# PCB.net
KiCad netlist of a schematic drawn in EAGLE
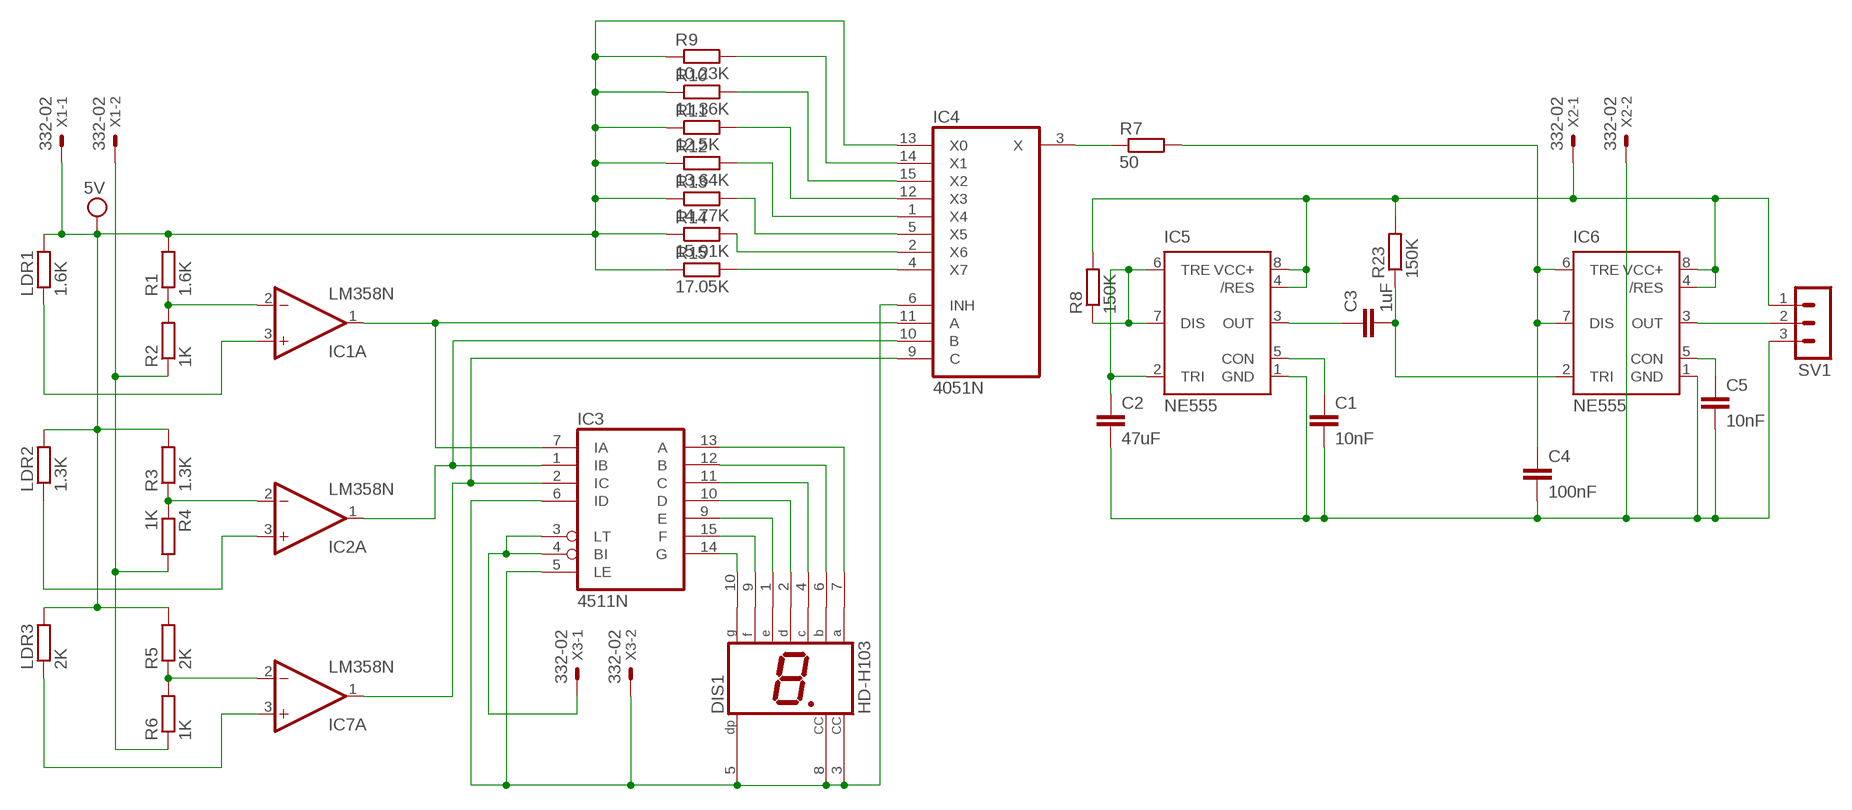
[diagram p0: schematic, sheet 1]

(export (version "E")
  (design (tool "Eeschema 10.0.6"))
  (components
    (comp (ref "C1")
      (value "10nF")
      (footprint "eagle-import:C2.5-2")
      (libsource (lib "eagle-import") (part "C2.5/2"))
    )
    (comp (ref "C2")
      (value "47uF")
      (footprint "eagle-import:C2.5-2")
      (libsource (lib "eagle-import") (part "C2.5/2"))
    )
    (comp (ref "C3")
      (value "1uF")
      (footprint "eagle-import:C2.5-2")
      (libsource (lib "eagle-import") (part "C2.5/2"))
    )
    (comp (ref "C4")
      (value "100nF")
      (footprint "eagle-import:C2.5-2")
      (libsource (lib "eagle-import") (part "C2.5/2"))
    )
    (comp (ref "C5")
      (value "10nF")
      (footprint "eagle-import:C2.5-2")
      (libsource (lib "eagle-import") (part "C2.5/2"))
    )
    (comp (ref "DIS1")
      (value "HD-H103")
      (footprint "eagle-import:HDSP-M")
      (libsource (lib "eagle-import") (part "HD-H103"))
    )
    (comp (ref "IC1")
      (value "LM358N")
      (footprint "eagle-import:DIL08")
      (libsource (lib "eagle-import") (part "LM358N"))
    )
    (comp (ref "IC2")
      (value "LM358N")
      (footprint "eagle-import:DIL08")
      (libsource (lib "eagle-import") (part "LM358N"))
    )
    (comp (ref "IC3")
      (value "4511N")
      (footprint "eagle-import:DIL16")
      (libsource (lib "eagle-import") (part "4511N"))
    )
    (comp (ref "IC4")
      (value "4051N")
      (footprint "eagle-import:DIL16")
      (libsource (lib "eagle-import") (part "4051N"))
    )
    (comp (ref "IC5")
      (value "NE555")
      (footprint "eagle-import:DIL-08")
      (fields (field (name "MF") "Arrow Electronics") (field (name "MPN") "NE555N"))
      (libsource (lib "eagle-import") (part "NE555"))
    )
    (comp (ref "IC6")
      (value "NE555")
      (footprint "eagle-import:DIL-08")
      (fields (field (name "MF") "Arrow Electronics") (field (name "MPN") "NE555N"))
      (libsource (lib "eagle-import") (part "NE555"))
    )
    (comp (ref "IC7")
      (value "LM358N")
      (footprint "eagle-import:DIL08")
      (libsource (lib "eagle-import") (part "LM358N"))
    )
    (comp (ref "LDR1")
      (value "1.6K")
      (footprint "eagle-import:0207_10")
      (libsource (lib "eagle-import") (part "R-EU_0207/10"))
    )
    (comp (ref "LDR2")
      (value "1.3K")
      (footprint "eagle-import:0207_10")
      (libsource (lib "eagle-import") (part "R-EU_0207/10"))
    )
    (comp (ref "LDR3")
      (value "2K")
      (footprint "eagle-import:0207_10")
      (libsource (lib "eagle-import") (part "R-EU_0207/10"))
    )
    (comp (ref "R1")
      (value "1.6K")
      (footprint "eagle-import:0207_10")
      (libsource (lib "eagle-import") (part "R-EU_0207/10"))
    )
    (comp (ref "R2")
      (value "1K")
      (footprint "eagle-import:0207_10")
      (libsource (lib "eagle-import") (part "R-EU_0207/10"))
    )
    (comp (ref "R3")
      (value "1.3K")
      (footprint "eagle-import:0207_10")
      (libsource (lib "eagle-import") (part "R-EU_0207/10"))
    )
    (comp (ref "R4")
      (value "1K")
      (footprint "eagle-import:0207_10")
      (libsource (lib "eagle-import") (part "R-EU_0207/10"))
    )
    (comp (ref "R5")
      (value "2K")
      (footprint "eagle-import:0207_10")
      (libsource (lib "eagle-import") (part "R-EU_0207/10"))
    )
    (comp (ref "R6")
      (value "1K")
      (footprint "eagle-import:0207_10")
      (libsource (lib "eagle-import") (part "R-EU_0207/10"))
    )
    (comp (ref "R7")
      (value "50")
      (footprint "eagle-import:0207_10")
      (libsource (lib "eagle-import") (part "R-EU_0207/10"))
    )
    (comp (ref "R8")
      (value "150K")
      (footprint "eagle-import:0207_10")
      (libsource (lib "eagle-import") (part "R-EU_0207/10"))
    )
    (comp (ref "R9")
      (value "10.23K")
      (footprint "eagle-import:0207_10")
      (libsource (lib "eagle-import") (part "R-EU_0207/10"))
    )
    (comp (ref "R10")
      (value "11.36K")
      (footprint "eagle-import:0207_10")
      (libsource (lib "eagle-import") (part "R-EU_0207/10"))
    )
    (comp (ref "R11")
      (value "12.5K")
      (footprint "eagle-import:0207_10")
      (libsource (lib "eagle-import") (part "R-EU_0207/10"))
    )
    (comp (ref "R12")
      (value "13.64K")
      (footprint "eagle-import:0207_10")
      (libsource (lib "eagle-import") (part "R-EU_0207/10"))
    )
    (comp (ref "R13")
      (value "14.77K")
      (footprint "eagle-import:0207_10")
      (libsource (lib "eagle-import") (part "R-EU_0207/10"))
    )
    (comp (ref "R14")
      (value "15.91K")
      (footprint "eagle-import:0207_10")
      (libsource (lib "eagle-import") (part "R-EU_0207/10"))
    )
    (comp (ref "R15")
      (value "17.05K")
      (footprint "eagle-import:0207_10")
      (libsource (lib "eagle-import") (part "R-EU_0207/10"))
    )
    (comp (ref "R23")
      (value "150K")
      (footprint "eagle-import:0207_10")
      (libsource (lib "eagle-import") (part "R-EU_0207/10"))
    )
    (comp (ref "SV1")
      (value "MA03-1")
      (footprint "eagle-import:MA03-1")
      (libsource (lib "eagle-import") (part "MA03-1"))
    )
    (comp (ref "X1")
      (value "332-02")
      (footprint "eagle-import:332-02")
      (libsource (lib "eagle-import") (part "332-02"))
    )
    (comp (ref "X2")
      (value "332-02")
      (footprint "eagle-import:332-02")
      (libsource (lib "eagle-import") (part "332-02"))
    )
    (comp (ref "X3")
      (value "332-02")
      (footprint "eagle-import:332-02")
      (libsource (lib "eagle-import") (part "332-02"))
    )
  )
  (nets
    (net (code "1") (name "5V") (class "Default")
      (node (ref "IC4") (pin "13") (pinfunction "X0_13") (pintype "bidirectional"))
      (node (ref "LDR1") (pin "2") (pinfunction "2_2") (pintype "passive"))
      (node (ref "LDR2") (pin "2") (pinfunction "2_2") (pintype "passive"))
      (node (ref "LDR3") (pin "2") (pinfunction "2_2") (pintype "passive"))
      (node (ref "R1") (pin "2") (pinfunction "2_2") (pintype "passive"))
      (node (ref "R10") (pin "1") (pinfunction "1_1") (pintype "passive"))
      (node (ref "R11") (pin "1") (pinfunction "1_1") (pintype "passive"))
      (node (ref "R12") (pin "1") (pinfunction "1_1") (pintype "passive"))
      (node (ref "R13") (pin "1") (pinfunction "1_1") (pintype "passive"))
      (node (ref "R14") (pin "1") (pinfunction "1_1") (pintype "passive"))
      (node (ref "R15") (pin "1") (pinfunction "1_1") (pintype "passive"))
      (node (ref "R3") (pin "2") (pinfunction "2_2") (pintype "passive"))
      (node (ref "R5") (pin "2") (pinfunction "2_2") (pintype "passive"))
      (node (ref "R9") (pin "1") (pinfunction "1_1") (pintype "passive"))
      (node (ref "X1") (pin "1") (pinfunction "S_1") (pintype "passive"))
    )
    (net (code "2") (name "Net-(DIS1-A)") (class "Default")
      (node (ref "DIS1") (pin "7") (pinfunction "A_7") (pintype "passive"))
      (node (ref "IC3") (pin "13") (pinfunction "A_13") (pintype "output"))
    )
    (net (code "3") (name "Net-(DIS1-B)") (class "Default")
      (node (ref "DIS1") (pin "6") (pinfunction "B_6") (pintype "passive"))
      (node (ref "IC3") (pin "12") (pinfunction "B_12") (pintype "output"))
    )
    (net (code "4") (name "Net-(DIS1-C)") (class "Default")
      (node (ref "DIS1") (pin "4") (pinfunction "C_4") (pintype "passive"))
      (node (ref "IC3") (pin "11") (pinfunction "C_11") (pintype "output"))
    )
    (net (code "5") (name "Net-(DIS1-D)") (class "Default")
      (node (ref "DIS1") (pin "2") (pinfunction "D_2") (pintype "passive"))
      (node (ref "IC3") (pin "10") (pinfunction "D_10") (pintype "output"))
    )
    (net (code "6") (name "Net-(DIS1-DP)") (class "Default")
      (node (ref "DIS1") (pin "3") (pinfunction "CC_3") (pintype "passive"))
      (node (ref "DIS1") (pin "5") (pinfunction "DP_5") (pintype "passive"))
      (node (ref "DIS1") (pin "8") (pinfunction "CC_8") (pintype "passive"))
      (node (ref "IC3") (pin "5") (pinfunction "LE_5") (pintype "input"))
      (node (ref "IC3") (pin "6") (pinfunction "ID_6") (pintype "input"))
      (node (ref "IC4") (pin "6") (pinfunction "INH_6") (pintype "input"))
      (node (ref "X3") (pin "2") (pinfunction "S_2") (pintype "passive"))
    )
    (net (code "7") (name "Net-(DIS1-E)") (class "Default")
      (node (ref "DIS1") (pin "1") (pinfunction "E_1") (pintype "passive"))
      (node (ref "IC3") (pin "9") (pinfunction "E_9") (pintype "output"))
    )
    (net (code "8") (name "Net-(DIS1-F)") (class "Default")
      (node (ref "DIS1") (pin "9") (pinfunction "F_9") (pintype "passive"))
      (node (ref "IC3") (pin "15") (pinfunction "F_15") (pintype "output"))
    )
    (net (code "9") (name "Net-(DIS1-G)") (class "Default")
      (node (ref "DIS1") (pin "10") (pinfunction "G_10") (pintype "passive"))
      (node (ref "IC3") (pin "14") (pinfunction "G_14") (pintype "output"))
    )
    (net (code "10") (name "Net-(IC1A-+IN)") (class "Default")
      (node (ref "IC1") (pin "3") (pinfunction "+IN_3") (pintype "input"))
      (node (ref "LDR1") (pin "1") (pinfunction "1_1") (pintype "passive"))
    )
    (net (code "11") (name "Net-(IC1A--IN)") (class "Default")
      (node (ref "IC1") (pin "2") (pinfunction "-IN_2") (pintype "input"))
      (node (ref "R1") (pin "1") (pinfunction "1_1") (pintype "passive"))
      (node (ref "R2") (pin "2") (pinfunction "2_2") (pintype "passive"))
    )
    (net (code "12") (name "Net-(IC1A-OUT)") (class "Default")
      (node (ref "IC1") (pin "1") (pinfunction "OUT_1") (pintype "output"))
      (node (ref "IC3") (pin "7") (pinfunction "IA_7") (pintype "input"))
      (node (ref "IC4") (pin "11") (pinfunction "A_11") (pintype "input"))
    )
    (net (code "13") (name "Net-(IC2A-+IN)") (class "Default")
      (node (ref "IC2") (pin "3") (pinfunction "+IN_3") (pintype "input"))
      (node (ref "LDR2") (pin "1") (pinfunction "1_1") (pintype "passive"))
    )
    (net (code "14") (name "Net-(IC2A--IN)") (class "Default")
      (node (ref "IC2") (pin "2") (pinfunction "-IN_2") (pintype "input"))
      (node (ref "R3") (pin "1") (pinfunction "1_1") (pintype "passive"))
      (node (ref "R4") (pin "1") (pinfunction "1_1") (pintype "passive"))
    )
    (net (code "15") (name "Net-(IC2A-OUT)") (class "Default")
      (node (ref "IC2") (pin "1") (pinfunction "OUT_1") (pintype "output"))
      (node (ref "IC3") (pin "1") (pinfunction "IB_1") (pintype "input"))
      (node (ref "IC4") (pin "10") (pinfunction "B_10") (pintype "input"))
    )
    (net (code "16") (name "Net-(IC3A-BI)") (class "Default")
      (node (ref "IC3") (pin "3") (pinfunction "LT_3") (pintype "input"))
      (node (ref "IC3") (pin "4") (pinfunction "BI_4") (pintype "input"))
      (node (ref "X3") (pin "1") (pinfunction "S_1") (pintype "passive"))
    )
    (net (code "17") (name "Net-(IC3A-IC)") (class "Default")
      (node (ref "IC3") (pin "2") (pinfunction "IC_2") (pintype "input"))
      (node (ref "IC4") (pin "9") (pinfunction "C_9") (pintype "input"))
      (node (ref "IC7") (pin "1") (pinfunction "OUT_1") (pintype "output"))
    )
    (net (code "18") (name "Net-(IC4A-X)") (class "Default")
      (node (ref "IC4") (pin "3") (pinfunction "X_3") (pintype "bidirectional"))
      (node (ref "R7") (pin "1") (pinfunction "1_1") (pintype "passive"))
    )
    (net (code "19") (name "Net-(IC4A-X1)") (class "Default")
      (node (ref "IC4") (pin "14") (pinfunction "X1_14") (pintype "bidirectional"))
      (node (ref "R9") (pin "2") (pinfunction "2_2") (pintype "passive"))
    )
    (net (code "20") (name "Net-(IC4A-X2)") (class "Default")
      (node (ref "IC4") (pin "15") (pinfunction "X2_15") (pintype "bidirectional"))
      (node (ref "R10") (pin "2") (pinfunction "2_2") (pintype "passive"))
    )
    (net (code "21") (name "Net-(IC4A-X3)") (class "Default")
      (node (ref "IC4") (pin "12") (pinfunction "X3_12") (pintype "bidirectional"))
      (node (ref "R11") (pin "2") (pinfunction "2_2") (pintype "passive"))
    )
    (net (code "22") (name "Net-(IC4A-X4)") (class "Default")
      (node (ref "IC4") (pin "1") (pinfunction "X4_1") (pintype "bidirectional"))
      (node (ref "R12") (pin "2") (pinfunction "2_2") (pintype "passive"))
    )
    (net (code "23") (name "Net-(IC4A-X5)") (class "Default")
      (node (ref "IC4") (pin "5") (pinfunction "X5_5") (pintype "bidirectional"))
      (node (ref "R13") (pin "2") (pinfunction "2_2") (pintype "passive"))
    )
    (net (code "24") (name "Net-(IC4A-X6)") (class "Default")
      (node (ref "IC4") (pin "2") (pinfunction "X6_2") (pintype "bidirectional"))
      (node (ref "R14") (pin "2") (pinfunction "2_2") (pintype "passive"))
    )
    (net (code "25") (name "Net-(IC4A-X7)") (class "Default")
      (node (ref "IC4") (pin "4") (pinfunction "X7_4") (pintype "bidirectional"))
      (node (ref "R15") (pin "2") (pinfunction "2_2") (pintype "passive"))
    )
    (net (code "26") (name "Net-(IC5-CON)") (class "Default")
      (node (ref "C1") (pin "1") (pinfunction "1_1") (pintype "passive"))
      (node (ref "IC5") (pin "5") (pinfunction "CON_5") (pintype "input"))
    )
    (net (code "27") (name "Net-(IC5-DIS)") (class "Default")
      (node (ref "C2") (pin "1") (pinfunction "1_1") (pintype "passive"))
      (node (ref "IC5") (pin "2") (pinfunction "TRI_2") (pintype "input"))
      (node (ref "IC5") (pin "6") (pinfunction "TRE_6") (pintype "input"))
      (node (ref "IC5") (pin "7") (pinfunction "DIS_7") (pintype "input"))
      (node (ref "R8") (pin "1") (pinfunction "1_1") (pintype "passive"))
    )
    (net (code "28") (name "Net-(IC5-GND)") (class "Default")
      (node (ref "C1") (pin "2") (pinfunction "2_2") (pintype "passive"))
      (node (ref "C2") (pin "2") (pinfunction "2_2") (pintype "passive"))
      (node (ref "C4") (pin "2") (pinfunction "2_2") (pintype "passive"))
      (node (ref "C5") (pin "2") (pinfunction "2_2") (pintype "passive"))
      (node (ref "IC5") (pin "1") (pinfunction "GND_1") (pintype "power_in"))
      (node (ref "IC6") (pin "1") (pinfunction "GND_1") (pintype "power_in"))
      (node (ref "SV1") (pin "3") (pinfunction "3_3") (pintype "passive"))
      (node (ref "X2") (pin "2") (pinfunction "S_2") (pintype "passive"))
    )
    (net (code "29") (name "Net-(IC5-OUT)") (class "Default")
      (node (ref "C3") (pin "1") (pinfunction "1_1") (pintype "passive"))
      (node (ref "IC5") (pin "3") (pinfunction "OUT_3") (pintype "output"))
    )
    (net (code "30") (name "Net-(IC5-VCC+)") (class "Default")
      (node (ref "IC5") (pin "4") (pinfunction "/RES_4") (pintype "input"))
      (node (ref "IC5") (pin "8") (pinfunction "VCC+_8") (pintype "power_in"))
      (node (ref "IC6") (pin "4") (pinfunction "/RES_4") (pintype "input"))
      (node (ref "IC6") (pin "8") (pinfunction "VCC+_8") (pintype "power_in"))
      (node (ref "R23") (pin "2") (pinfunction "2_2") (pintype "passive"))
      (node (ref "R8") (pin "2") (pinfunction "2_2") (pintype "passive"))
      (node (ref "SV1") (pin "1") (pinfunction "1_1") (pintype "passive"))
      (node (ref "X2") (pin "1") (pinfunction "S_1") (pintype "passive"))
    )
    (net (code "31") (name "Net-(IC6-CON)") (class "Default")
      (node (ref "C5") (pin "1") (pinfunction "1_1") (pintype "passive"))
      (node (ref "IC6") (pin "5") (pinfunction "CON_5") (pintype "input"))
    )
    (net (code "32") (name "Net-(IC6-DIS)") (class "Default")
      (node (ref "C4") (pin "1") (pinfunction "1_1") (pintype "passive"))
      (node (ref "IC6") (pin "6") (pinfunction "TRE_6") (pintype "input"))
      (node (ref "IC6") (pin "7") (pinfunction "DIS_7") (pintype "input"))
      (node (ref "R7") (pin "2") (pinfunction "2_2") (pintype "passive"))
    )
    (net (code "33") (name "Net-(IC6-OUT)") (class "Default")
      (node (ref "IC6") (pin "3") (pinfunction "OUT_3") (pintype "output"))
      (node (ref "SV1") (pin "2") (pinfunction "2_2") (pintype "passive"))
    )
    (net (code "34") (name "Net-(IC6-TRI)") (class "Default")
      (node (ref "C3") (pin "2") (pinfunction "2_2") (pintype "passive"))
      (node (ref "IC6") (pin "2") (pinfunction "TRI_2") (pintype "input"))
      (node (ref "R23") (pin "1") (pinfunction "1_1") (pintype "passive"))
    )
    (net (code "35") (name "Net-(IC7A-+IN)") (class "Default")
      (node (ref "IC7") (pin "3") (pinfunction "+IN_3") (pintype "input"))
      (node (ref "LDR3") (pin "1") (pinfunction "1_1") (pintype "passive"))
    )
    (net (code "36") (name "Net-(IC7A--IN)") (class "Default")
      (node (ref "IC7") (pin "2") (pinfunction "-IN_2") (pintype "input"))
      (node (ref "R5") (pin "1") (pinfunction "1_1") (pintype "passive"))
      (node (ref "R6") (pin "2") (pinfunction "2_2") (pintype "passive"))
    )
    (net (code "37") (name "Net-(X1B-S)") (class "Default")
      (node (ref "R2") (pin "1") (pinfunction "1_1") (pintype "passive"))
      (node (ref "R4") (pin "2") (pinfunction "2_2") (pintype "passive"))
      (node (ref "R6") (pin "1") (pinfunction "1_1") (pintype "passive"))
      (node (ref "X1") (pin "2") (pinfunction "S_2") (pintype "passive"))
    )
  )
)
